# clock02.net
KiCad netlist of a schematic drawn in EAGLE
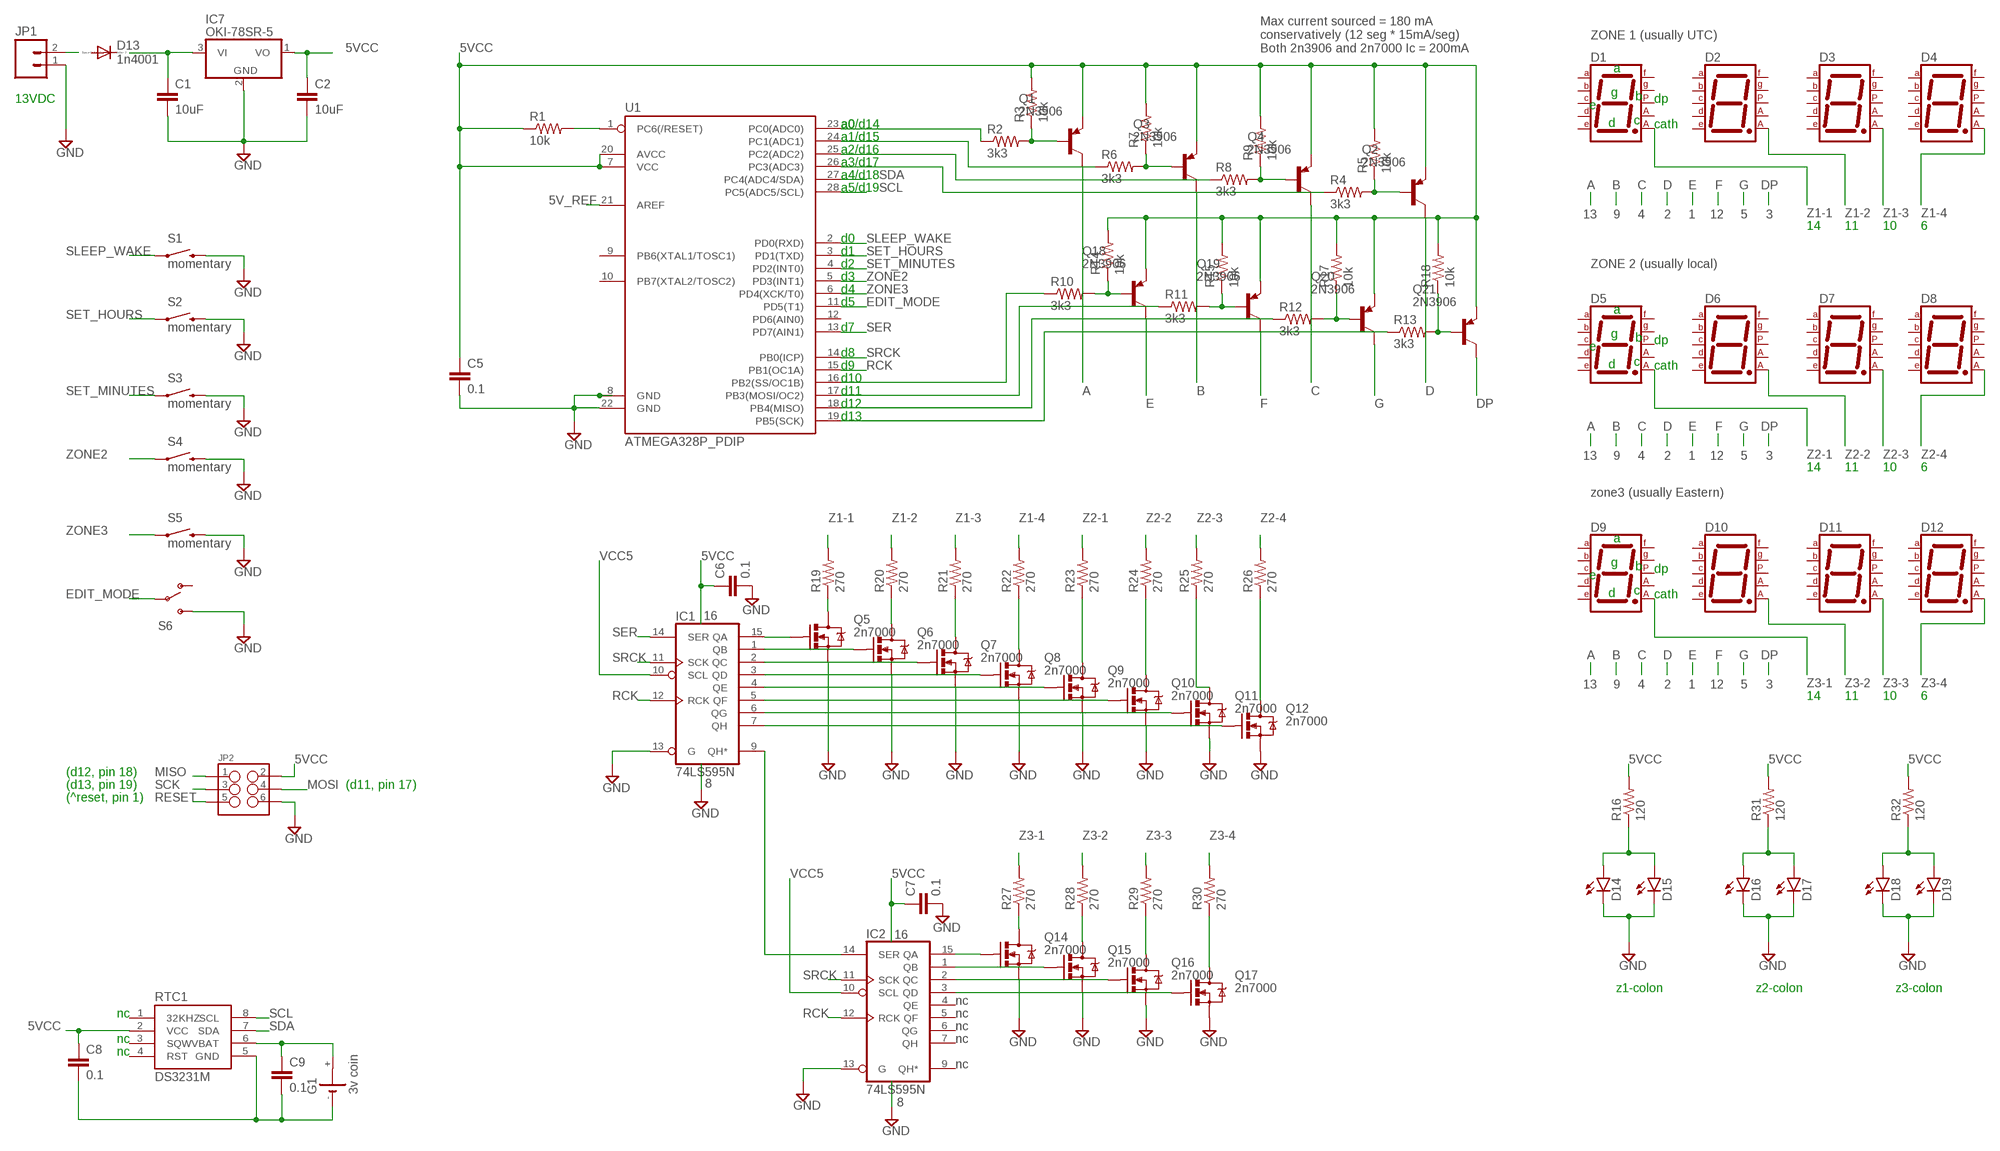
[diagram p0: schematic, sheet 1]

(export (version "E")
  (design (tool "Eeschema 10.0.6"))
  (components
    (comp (ref "C1")
      (value "10uF")
      (footprint "eagle-import:0603-CAP")
      (libsource (lib "eagle-import") (part "10NF/10000PF-50V-10%(0603)"))
    )
    (comp (ref "C2")
      (value "10uF")
      (footprint "eagle-import:0603-CAP")
      (libsource (lib "eagle-import") (part "10NF/10000PF-50V-10%(0603)"))
    )
    (comp (ref "C5")
      (value "0.1")
      (footprint "eagle-import:0603-CAP")
      (libsource (lib "eagle-import") (part "10NF/10000PF-50V-10%(0603)"))
    )
    (comp (ref "C6")
      (value "0.1")
      (footprint "eagle-import:0603-CAP")
      (libsource (lib "eagle-import") (part "10NF/10000PF-50V-10%(0603)"))
    )
    (comp (ref "C7")
      (value "0.1")
      (footprint "eagle-import:0603-CAP")
      (libsource (lib "eagle-import") (part "10NF/10000PF-50V-10%(0603)"))
    )
    (comp (ref "C8")
      (value "0.1")
      (footprint "eagle-import:0603-CAP")
      (libsource (lib "eagle-import") (part "10NF/10000PF-50V-10%(0603)"))
    )
    (comp (ref "C9")
      (value "0.1")
      (footprint "eagle-import:0603-CAP")
      (libsource (lib "eagle-import") (part "10NF/10000PF-50V-10%(0603)"))
    )
    (comp (ref "D1")
      (value "7SEG-CA")
      (footprint "eagle-import:7SEG-13")
      (libsource (lib "eagle-import") (part "7SEG-CA"))
    )
    (comp (ref "D2")
      (value "7SEG-CA")
      (footprint "eagle-import:7SEG-13")
      (libsource (lib "eagle-import") (part "7SEG-CA"))
    )
    (comp (ref "D3")
      (value "7SEG-CA")
      (footprint "eagle-import:7SEG-13")
      (libsource (lib "eagle-import") (part "7SEG-CA"))
    )
    (comp (ref "D4")
      (value "7SEG-CA")
      (footprint "eagle-import:7SEG-13")
      (libsource (lib "eagle-import") (part "7SEG-CA"))
    )
    (comp (ref "D5")
      (value "7SEG-CA")
      (footprint "eagle-import:7SEG-13")
      (libsource (lib "eagle-import") (part "7SEG-CA"))
    )
    (comp (ref "D6")
      (value "7SEG-CA")
      (footprint "eagle-import:7SEG-13")
      (libsource (lib "eagle-import") (part "7SEG-CA"))
    )
    (comp (ref "D7")
      (value "7SEG-CA")
      (footprint "eagle-import:7SEG-13")
      (libsource (lib "eagle-import") (part "7SEG-CA"))
    )
    (comp (ref "D8")
      (value "7SEG-CA")
      (footprint "eagle-import:7SEG-13")
      (libsource (lib "eagle-import") (part "7SEG-CA"))
    )
    (comp (ref "D9")
      (value "7SEG-CA")
      (footprint "eagle-import:7SEG-13")
      (libsource (lib "eagle-import") (part "7SEG-CA"))
    )
    (comp (ref "D10")
      (value "7SEG-CA")
      (footprint "eagle-import:7SEG-13")
      (libsource (lib "eagle-import") (part "7SEG-CA"))
    )
    (comp (ref "D11")
      (value "7SEG-CA")
      (footprint "eagle-import:7SEG-13")
      (libsource (lib "eagle-import") (part "7SEG-CA"))
    )
    (comp (ref "D12")
      (value "7SEG-CA")
      (footprint "eagle-import:7SEG-13")
      (libsource (lib "eagle-import") (part "7SEG-CA"))
    )
    (comp (ref "D13")
      (value "1n4001")
      (footprint "eagle-import:DO41-10")
      (libsource (lib "eagle-import") (part "1N4004"))
    )
    (comp (ref "D14")
      (value "LED3MM")
      (footprint "eagle-import:LED3MM")
      (libsource (lib "eagle-import") (part "LED3MM"))
    )
    (comp (ref "D15")
      (value "LED3MM")
      (footprint "eagle-import:LED3MM")
      (libsource (lib "eagle-import") (part "LED3MM"))
    )
    (comp (ref "D16")
      (value "LED3MM")
      (footprint "eagle-import:LED3MM")
      (libsource (lib "eagle-import") (part "LED3MM"))
    )
    (comp (ref "D17")
      (value "LED3MM")
      (footprint "eagle-import:LED3MM")
      (libsource (lib "eagle-import") (part "LED3MM"))
    )
    (comp (ref "D18")
      (value "LED3MM")
      (footprint "eagle-import:LED3MM")
      (libsource (lib "eagle-import") (part "LED3MM"))
    )
    (comp (ref "D19")
      (value "LED3MM")
      (footprint "eagle-import:LED3MM")
      (libsource (lib "eagle-import") (part "LED3MM"))
    )
    (comp (ref "G1")
      (value "3v coin")
      (footprint "eagle-import:CR2032H")
      (libsource (lib "eagle-import") (part "CR2032H"))
    )
    (comp (ref "IC1")
      (value "74LS595N")
      (footprint "eagle-import:DIL16")
      (libsource (lib "eagle-import") (part "74595NLS"))
    )
    (comp (ref "IC2")
      (value "74LS595N")
      (footprint "eagle-import:DIL16")
      (libsource (lib "eagle-import") (part "74595NLS"))
    )
    (comp (ref "IC7")
      (value "OKI-78SR-5")
      (footprint "eagle-import:TO92")
      (libsource (lib "eagle-import") (part "78ZL05"))
    )
    (comp (ref "JP1")
      (value "M02-JST-2-PTH-NO_SILK")
      (footprint "eagle-import:JST-2-PTH-NS")
      (libsource (lib "eagle-import") (part "M02-JST-2-PTH-NO_SILK"))
    )
    (comp (ref "JP2")
      (value "M03X2")
      (footprint "eagle-import:2X3_SMD")
      (libsource (lib "eagle-import") (part "M03X2"))
    )
    (comp (ref "Q1")
      (value "2N3906")
      (footprint "eagle-import:TO92")
      (libsource (lib "eagle-import") (part "2N3906"))
    )
    (comp (ref "Q2")
      (value "2N3906")
      (footprint "eagle-import:TO92")
      (libsource (lib "eagle-import") (part "2N3906"))
    )
    (comp (ref "Q3")
      (value "2N3906")
      (footprint "eagle-import:TO92")
      (libsource (lib "eagle-import") (part "2N3906"))
    )
    (comp (ref "Q4")
      (value "2N3906")
      (footprint "eagle-import:TO92")
      (libsource (lib "eagle-import") (part "2N3906"))
    )
    (comp (ref "Q5")
      (value "2n7000")
      (footprint "eagle-import:TO-92")
      (libsource (lib "eagle-import") (part "MOSFET-NCHANNEL2N7000"))
    )
    (comp (ref "Q6")
      (value "2n7000")
      (footprint "eagle-import:TO-92")
      (libsource (lib "eagle-import") (part "MOSFET-NCHANNEL2N7000"))
    )
    (comp (ref "Q7")
      (value "2n7000")
      (footprint "eagle-import:TO-92")
      (libsource (lib "eagle-import") (part "MOSFET-NCHANNEL2N7000"))
    )
    (comp (ref "Q8")
      (value "2n7000")
      (footprint "eagle-import:TO-92")
      (libsource (lib "eagle-import") (part "MOSFET-NCHANNEL2N7000"))
    )
    (comp (ref "Q9")
      (value "2n7000")
      (footprint "eagle-import:TO-92")
      (libsource (lib "eagle-import") (part "MOSFET-NCHANNEL2N7000"))
    )
    (comp (ref "Q10")
      (value "2n7000")
      (footprint "eagle-import:TO-92")
      (libsource (lib "eagle-import") (part "MOSFET-NCHANNEL2N7000"))
    )
    (comp (ref "Q11")
      (value "2n7000")
      (footprint "eagle-import:TO-92")
      (libsource (lib "eagle-import") (part "MOSFET-NCHANNEL2N7000"))
    )
    (comp (ref "Q12")
      (value "2n7000")
      (footprint "eagle-import:TO-92")
      (libsource (lib "eagle-import") (part "MOSFET-NCHANNEL2N7000"))
    )
    (comp (ref "Q14")
      (value "2n7000")
      (footprint "eagle-import:TO-92")
      (libsource (lib "eagle-import") (part "MOSFET-NCHANNEL2N7000"))
    )
    (comp (ref "Q15")
      (value "2n7000")
      (footprint "eagle-import:TO-92")
      (libsource (lib "eagle-import") (part "MOSFET-NCHANNEL2N7000"))
    )
    (comp (ref "Q16")
      (value "2n7000")
      (footprint "eagle-import:TO-92")
      (libsource (lib "eagle-import") (part "MOSFET-NCHANNEL2N7000"))
    )
    (comp (ref "Q17")
      (value "2n7000")
      (footprint "eagle-import:TO-92")
      (libsource (lib "eagle-import") (part "MOSFET-NCHANNEL2N7000"))
    )
    (comp (ref "Q18")
      (value "2N3906")
      (footprint "eagle-import:TO92")
      (libsource (lib "eagle-import") (part "2N3906"))
    )
    (comp (ref "Q19")
      (value "2N3906")
      (footprint "eagle-import:TO92")
      (libsource (lib "eagle-import") (part "2N3906"))
    )
    (comp (ref "Q20")
      (value "2N3906")
      (footprint "eagle-import:TO92")
      (libsource (lib "eagle-import") (part "2N3906"))
    )
    (comp (ref "Q21")
      (value "2N3906")
      (footprint "eagle-import:TO92")
      (libsource (lib "eagle-import") (part "2N3906"))
    )
    (comp (ref "R1")
      (value "10k")
      (footprint "eagle-import:AXIAL-0.3")
      (libsource (lib "eagle-import") (part "10KOHM-1/4W-1%(PTH)HORIZ"))
    )
    (comp (ref "R2")
      (value "3k3")
      (footprint "eagle-import:AXIAL-0.3")
      (libsource (lib "eagle-import") (part "10KOHM-1/4W-1%(PTH)HORIZ"))
    )
    (comp (ref "R3")
      (value "10k")
      (footprint "eagle-import:AXIAL-0.3")
      (libsource (lib "eagle-import") (part "10KOHM-1/4W-1%(PTH)HORIZ"))
    )
    (comp (ref "R4")
      (value "3k3")
      (footprint "eagle-import:AXIAL-0.3")
      (libsource (lib "eagle-import") (part "10KOHM-1/4W-1%(PTH)HORIZ"))
    )
    (comp (ref "R5")
      (value "10k")
      (footprint "eagle-import:AXIAL-0.3")
      (libsource (lib "eagle-import") (part "10KOHM-1/4W-1%(PTH)HORIZ"))
    )
    (comp (ref "R6")
      (value "3k3")
      (footprint "eagle-import:AXIAL-0.3")
      (libsource (lib "eagle-import") (part "10KOHM-1/4W-1%(PTH)HORIZ"))
    )
    (comp (ref "R7")
      (value "10k")
      (footprint "eagle-import:AXIAL-0.3")
      (libsource (lib "eagle-import") (part "10KOHM-1/4W-1%(PTH)HORIZ"))
    )
    (comp (ref "R8")
      (value "3k3")
      (footprint "eagle-import:AXIAL-0.3")
      (libsource (lib "eagle-import") (part "10KOHM-1/4W-1%(PTH)HORIZ"))
    )
    (comp (ref "R9")
      (value "10k")
      (footprint "eagle-import:AXIAL-0.3")
      (libsource (lib "eagle-import") (part "10KOHM-1/4W-1%(PTH)HORIZ"))
    )
    (comp (ref "R10")
      (value "3k3")
      (footprint "eagle-import:AXIAL-0.3")
      (libsource (lib "eagle-import") (part "10KOHM-1/4W-1%(PTH)HORIZ"))
    )
    (comp (ref "R11")
      (value "3k3")
      (footprint "eagle-import:AXIAL-0.3")
      (libsource (lib "eagle-import") (part "10KOHM-1/4W-1%(PTH)HORIZ"))
    )
    (comp (ref "R12")
      (value "3k3")
      (footprint "eagle-import:AXIAL-0.3")
      (libsource (lib "eagle-import") (part "10KOHM-1/4W-1%(PTH)HORIZ"))
    )
    (comp (ref "R13")
      (value "3k3")
      (footprint "eagle-import:AXIAL-0.3")
      (libsource (lib "eagle-import") (part "10KOHM-1/4W-1%(PTH)HORIZ"))
    )
    (comp (ref "R14")
      (value "10k")
      (footprint "eagle-import:AXIAL-0.3")
      (libsource (lib "eagle-import") (part "10KOHM-1/4W-1%(PTH)HORIZ"))
    )
    (comp (ref "R15")
      (value "10k")
      (footprint "eagle-import:AXIAL-0.3")
      (libsource (lib "eagle-import") (part "10KOHM-1/4W-1%(PTH)HORIZ"))
    )
    (comp (ref "R16")
      (value "120")
      (footprint "eagle-import:AXIAL-0.3")
      (libsource (lib "eagle-import") (part "10KOHM-1/4W-1%(PTH)HORIZ"))
    )
    (comp (ref "R17")
      (value "10k")
      (footprint "eagle-import:AXIAL-0.3")
      (libsource (lib "eagle-import") (part "10KOHM-1/4W-1%(PTH)HORIZ"))
    )
    (comp (ref "R18")
      (value "10k")
      (footprint "eagle-import:AXIAL-0.3")
      (libsource (lib "eagle-import") (part "10KOHM-1/4W-1%(PTH)HORIZ"))
    )
    (comp (ref "R19")
      (value "270")
      (footprint "eagle-import:AXIAL-0.3")
      (libsource (lib "eagle-import") (part "10KOHM-1/4W-1%(PTH)HORIZ"))
    )
    (comp (ref "R20")
      (value "270")
      (footprint "eagle-import:AXIAL-0.3")
      (libsource (lib "eagle-import") (part "10KOHM-1/4W-1%(PTH)HORIZ"))
    )
    (comp (ref "R21")
      (value "270")
      (footprint "eagle-import:AXIAL-0.3")
      (libsource (lib "eagle-import") (part "10KOHM-1/4W-1%(PTH)HORIZ"))
    )
    (comp (ref "R22")
      (value "270")
      (footprint "eagle-import:AXIAL-0.3")
      (libsource (lib "eagle-import") (part "10KOHM-1/4W-1%(PTH)HORIZ"))
    )
    (comp (ref "R23")
      (value "270")
      (footprint "eagle-import:AXIAL-0.3")
      (libsource (lib "eagle-import") (part "10KOHM-1/4W-1%(PTH)HORIZ"))
    )
    (comp (ref "R24")
      (value "270")
      (footprint "eagle-import:AXIAL-0.3")
      (libsource (lib "eagle-import") (part "10KOHM-1/4W-1%(PTH)HORIZ"))
    )
    (comp (ref "R25")
      (value "270")
      (footprint "eagle-import:AXIAL-0.3")
      (libsource (lib "eagle-import") (part "10KOHM-1/4W-1%(PTH)HORIZ"))
    )
    (comp (ref "R26")
      (value "270")
      (footprint "eagle-import:AXIAL-0.3")
      (libsource (lib "eagle-import") (part "10KOHM-1/4W-1%(PTH)HORIZ"))
    )
    (comp (ref "R27")
      (value "270")
      (footprint "eagle-import:AXIAL-0.3")
      (libsource (lib "eagle-import") (part "10KOHM-1/4W-1%(PTH)HORIZ"))
    )
    (comp (ref "R28")
      (value "270")
      (footprint "eagle-import:AXIAL-0.3")
      (libsource (lib "eagle-import") (part "10KOHM-1/4W-1%(PTH)HORIZ"))
    )
    (comp (ref "R29")
      (value "270")
      (footprint "eagle-import:AXIAL-0.3")
      (libsource (lib "eagle-import") (part "10KOHM-1/4W-1%(PTH)HORIZ"))
    )
    (comp (ref "R30")
      (value "270")
      (footprint "eagle-import:AXIAL-0.3")
      (libsource (lib "eagle-import") (part "10KOHM-1/4W-1%(PTH)HORIZ"))
    )
    (comp (ref "R31")
      (value "120")
      (footprint "eagle-import:AXIAL-0.3")
      (libsource (lib "eagle-import") (part "10KOHM-1/4W-1%(PTH)HORIZ"))
    )
    (comp (ref "R32")
      (value "120")
      (footprint "eagle-import:AXIAL-0.3")
      (libsource (lib "eagle-import") (part "10KOHM-1/4W-1%(PTH)HORIZ"))
    )
    (comp (ref "RTC1")
      (value "DS3231M")
      (footprint "eagle-import:SOIC8")
      (libsource (lib "eagle-import") (part "DS3231M"))
    )
    (comp (ref "S1")
      (value "momentary")
      (footprint "eagle-import:REED_SWITCH_PTH")
      (libsource (lib "eagle-import") (part "SWITCH-MOMENTARY-2PTH_REED"))
    )
    (comp (ref "S2")
      (value "momentary")
      (footprint "eagle-import:REED_SWITCH_PTH")
      (libsource (lib "eagle-import") (part "SWITCH-MOMENTARY-2PTH_REED"))
    )
    (comp (ref "S3")
      (value "momentary")
      (footprint "eagle-import:REED_SWITCH_PTH")
      (libsource (lib "eagle-import") (part "SWITCH-MOMENTARY-2PTH_REED"))
    )
    (comp (ref "S4")
      (value "momentary")
      (footprint "eagle-import:REED_SWITCH_PTH")
      (libsource (lib "eagle-import") (part "SWITCH-MOMENTARY-2PTH_REED"))
    )
    (comp (ref "S5")
      (value "momentary")
      (footprint "eagle-import:REED_SWITCH_PTH")
      (libsource (lib "eagle-import") (part "SWITCH-MOMENTARY-2PTH_REED"))
    )
    (comp (ref "S6")
      (value "SWITCH-SPDTPTH")
      (footprint "eagle-import:SWITCH-SPDT")
      (libsource (lib "eagle-import") (part "SWITCH-SPDTPTH"))
    )
    (comp (ref "U1")
      (value "ATMEGA328P_PDIP")
      (footprint "eagle-import:DIL28-3")
      (libsource (lib "eagle-import") (part "ATMEGA328P_PDIP"))
    )
  )
  (nets
    (net (code "1") (name "/5VCC") (class "Default")
      (node (ref "C2") (pin "1") (pinfunction "1_1") (pintype "passive"))
      (node (ref "C5") (pin "1") (pinfunction "1_1") (pintype "passive"))
      (node (ref "C6") (pin "1") (pinfunction "1_1") (pintype "passive"))
      (node (ref "C7") (pin "1") (pinfunction "1_1") (pintype "passive"))
      (node (ref "C8") (pin "1") (pinfunction "1_1") (pintype "passive"))
      (node (ref "IC7") (pin "1") (pinfunction "VO_1") (pintype "passive"))
      (node (ref "JP2") (pin "2") (pinfunction "2_2") (pintype "bidirectional"))
      (node (ref "Q1") (pin "3") (pinfunction "E_3") (pintype "passive"))
      (node (ref "Q18") (pin "3") (pinfunction "E_3") (pintype "passive"))
      (node (ref "Q19") (pin "3") (pinfunction "E_3") (pintype "passive"))
      (node (ref "Q2") (pin "3") (pinfunction "E_3") (pintype "passive"))
      (node (ref "Q20") (pin "3") (pinfunction "E_3") (pintype "passive"))
      (node (ref "Q21") (pin "3") (pinfunction "E_3") (pintype "passive"))
      (node (ref "Q3") (pin "3") (pinfunction "E_3") (pintype "passive"))
      (node (ref "Q4") (pin "3") (pinfunction "E_3") (pintype "passive"))
      (node (ref "R1") (pin "P$1") (pinfunction "1_P$1") (pintype "passive"))
      (node (ref "R14") (pin "P$2") (pinfunction "2_P$2") (pintype "passive"))
      (node (ref "R15") (pin "P$2") (pinfunction "2_P$2") (pintype "passive"))
      (node (ref "R16") (pin "P$2") (pinfunction "2_P$2") (pintype "passive"))
      (node (ref "R17") (pin "P$2") (pinfunction "2_P$2") (pintype "passive"))
      (node (ref "R18") (pin "P$2") (pinfunction "2_P$2") (pintype "passive"))
      (node (ref "R3") (pin "P$2") (pinfunction "2_P$2") (pintype "passive"))
      (node (ref "R31") (pin "P$2") (pinfunction "2_P$2") (pintype "passive"))
      (node (ref "R32") (pin "P$2") (pinfunction "2_P$2") (pintype "passive"))
      (node (ref "R5") (pin "P$2") (pinfunction "2_P$2") (pintype "passive"))
      (node (ref "R7") (pin "P$2") (pinfunction "2_P$2") (pintype "passive"))
      (node (ref "R9") (pin "P$2") (pinfunction "2_P$2") (pintype "passive"))
      (node (ref "RTC1") (pin "2") (pinfunction "VCC_2") (pintype "power_in"))
      (node (ref "U1") (pin "20") (pinfunction "AVCC_20") (pintype "bidirectional"))
      (node (ref "U1") (pin "7") (pinfunction "VCC_7") (pintype "bidirectional"))
    )
    (net (code "2") (name "/5V_REF") (class "Default")
      (node (ref "U1") (pin "21") (pinfunction "AREF_21") (pintype "bidirectional"))
    )
    (net (code "3") (name "/A") (class "Default")
      (node (ref "Q1") (pin "1") (pinfunction "C_1") (pintype "passive"))
    )
    (net (code "4") (name "/B") (class "Default")
      (node (ref "Q3") (pin "1") (pinfunction "C_1") (pintype "passive"))
    )
    (net (code "5") (name "/C") (class "Default")
      (node (ref "Q4") (pin "1") (pinfunction "C_1") (pintype "passive"))
    )
    (net (code "6") (name "/D") (class "Default")
      (node (ref "Q2") (pin "1") (pinfunction "C_1") (pintype "passive"))
    )
    (net (code "7") (name "/DP") (class "Default")
      (node (ref "Q21") (pin "1") (pinfunction "C_1") (pintype "passive"))
    )
    (net (code "8") (name "/E") (class "Default")
      (node (ref "Q18") (pin "1") (pinfunction "C_1") (pintype "passive"))
    )
    (net (code "9") (name "/EDIT_MODE") (class "Default")
      (node (ref "S6") (pin "2") (pinfunction "P_2") (pintype "passive"))
      (node (ref "U1") (pin "11") (pinfunction "PD5(T1)_11") (pintype "bidirectional"))
    )
    (net (code "10") (name "/F") (class "Default")
      (node (ref "Q19") (pin "1") (pinfunction "C_1") (pintype "passive"))
    )
    (net (code "11") (name "/G") (class "Default")
      (node (ref "Q20") (pin "1") (pinfunction "C_1") (pintype "passive"))
    )
    (net (code "12") (name "/MISO") (class "Default")
      (node (ref "JP2") (pin "1") (pinfunction "1_1") (pintype "bidirectional"))
    )
    (net (code "13") (name "/MOSI") (class "Default")
      (node (ref "JP2") (pin "4") (pinfunction "4_4") (pintype "bidirectional"))
    )
    (net (code "14") (name "/RCK") (class "Default")
      (node (ref "IC1") (pin "12") (pinfunction "RCK_12") (pintype "input"))
      (node (ref "IC2") (pin "12") (pinfunction "RCK_12") (pintype "input"))
      (node (ref "U1") (pin "15") (pinfunction "PB1(OC1A)_15") (pintype "bidirectional"))
    )
    (net (code "15") (name "/RESET") (class "Default")
      (node (ref "JP2") (pin "5") (pinfunction "5_5") (pintype "bidirectional"))
    )
    (net (code "16") (name "/SCK") (class "Default")
      (node (ref "JP2") (pin "3") (pinfunction "3_3") (pintype "bidirectional"))
    )
    (net (code "17") (name "/SCL") (class "Default")
      (node (ref "RTC1") (pin "8") (pinfunction "SCL_8") (pintype "bidirectional"))
      (node (ref "U1") (pin "28") (pinfunction "PC5(ADC5/SCL)_28") (pintype "bidirectional"))
    )
    (net (code "18") (name "/SDA") (class "Default")
      (node (ref "RTC1") (pin "7") (pinfunction "SDA_7") (pintype "bidirectional"))
      (node (ref "U1") (pin "27") (pinfunction "PC4(ADC4/SDA)_27") (pintype "bidirectional"))
    )
    (net (code "19") (name "/SER") (class "Default")
      (node (ref "IC1") (pin "14") (pinfunction "SER_14") (pintype "input"))
      (node (ref "U1") (pin "13") (pinfunction "PD7(AIN1)_13") (pintype "bidirectional"))
    )
    (net (code "20") (name "/SET_HOURS") (class "Default")
      (node (ref "S2") (pin "P$1") (pinfunction "1_P$1") (pintype "passive"))
      (node (ref "U1") (pin "3") (pinfunction "PD1(TXD)_3") (pintype "bidirectional"))
    )
    (net (code "21") (name "/SET_MINUTES") (class "Default")
      (node (ref "S3") (pin "P$1") (pinfunction "1_P$1") (pintype "passive"))
      (node (ref "U1") (pin "4") (pinfunction "PD2(INT0)_4") (pintype "bidirectional"))
    )
    (net (code "22") (name "/SLEEP_WAKE") (class "Default")
      (node (ref "S1") (pin "P$1") (pinfunction "1_P$1") (pintype "passive"))
      (node (ref "U1") (pin "2") (pinfunction "PD0(RXD)_2") (pintype "bidirectional"))
    )
    (net (code "23") (name "/SRCK") (class "Default")
      (node (ref "IC1") (pin "11") (pinfunction "SCK_11") (pintype "input"))
      (node (ref "IC2") (pin "11") (pinfunction "SCK_11") (pintype "input"))
      (node (ref "U1") (pin "14") (pinfunction "PB0(ICP)_14") (pintype "bidirectional"))
    )
    (net (code "24") (name "/VCC5") (class "Default")
      (node (ref "IC1") (pin "10") (pinfunction "SCL_10") (pintype "input"))
      (node (ref "IC2") (pin "10") (pinfunction "SCL_10") (pintype "input"))
    )
    (net (code "25") (name "/Z1-1") (class "Default")
      (node (ref "D1") (pin "8") (pinfunction "CA2_8") (pintype "passive"))
      (node (ref "R19") (pin "P$2") (pinfunction "2_P$2") (pintype "passive"))
    )
    (net (code "26") (name "/Z1-2") (class "Default")
      (node (ref "D2") (pin "8") (pinfunction "CA2_8") (pintype "passive"))
      (node (ref "R20") (pin "P$2") (pinfunction "2_P$2") (pintype "passive"))
    )
    (net (code "27") (name "/Z1-3") (class "Default")
      (node (ref "D3") (pin "8") (pinfunction "CA2_8") (pintype "passive"))
      (node (ref "R21") (pin "P$2") (pinfunction "2_P$2") (pintype "passive"))
    )
    (net (code "28") (name "/Z1-4") (class "Default")
      (node (ref "D4") (pin "8") (pinfunction "CA2_8") (pintype "passive"))
      (node (ref "R22") (pin "P$2") (pinfunction "2_P$2") (pintype "passive"))
    )
    (net (code "29") (name "/Z2-1") (class "Default")
      (node (ref "D5") (pin "8") (pinfunction "CA2_8") (pintype "passive"))
      (node (ref "R23") (pin "P$2") (pinfunction "2_P$2") (pintype "passive"))
    )
    (net (code "30") (name "/Z2-2") (class "Default")
      (node (ref "D6") (pin "8") (pinfunction "CA2_8") (pintype "passive"))
      (node (ref "R24") (pin "P$2") (pinfunction "2_P$2") (pintype "passive"))
    )
    (net (code "31") (name "/Z2-3") (class "Default")
      (node (ref "D7") (pin "8") (pinfunction "CA2_8") (pintype "passive"))
      (node (ref "R25") (pin "P$2") (pinfunction "2_P$2") (pintype "passive"))
    )
    (net (code "32") (name "/Z2-4") (class "Default")
      (node (ref "D8") (pin "8") (pinfunction "CA2_8") (pintype "passive"))
      (node (ref "R26") (pin "P$2") (pinfunction "2_P$2") (pintype "passive"))
    )
    (net (code "33") (name "/Z3-1") (class "Default")
      (node (ref "D9") (pin "8") (pinfunction "CA2_8") (pintype "passive"))
      (node (ref "R27") (pin "P$2") (pinfunction "2_P$2") (pintype "passive"))
    )
    (net (code "34") (name "/Z3-2") (class "Default")
      (node (ref "D10") (pin "8") (pinfunction "CA2_8") (pintype "passive"))
      (node (ref "R28") (pin "P$2") (pinfunction "2_P$2") (pintype "passive"))
    )
    (net (code "35") (name "/Z3-3") (class "Default")
      (node (ref "D11") (pin "8") (pinfunction "CA2_8") (pintype "passive"))
      (node (ref "R29") (pin "P$2") (pinfunction "2_P$2") (pintype "passive"))
    )
    (net (code "36") (name "/Z3-4") (class "Default")
      (node (ref "D12") (pin "8") (pinfunction "CA2_8") (pintype "passive"))
      (node (ref "R30") (pin "P$2") (pinfunction "2_P$2") (pintype "passive"))
    )
    (net (code "37") (name "/ZONE2") (class "Default")
      (node (ref "S4") (pin "P$1") (pinfunction "1_P$1") (pintype "passive"))
      (node (ref "U1") (pin "5") (pinfunction "PD3(INT1)_5") (pintype "bidirectional"))
    )
    (net (code "38") (name "/ZONE3") (class "Default")
      (node (ref "S5") (pin "P$1") (pinfunction "1_P$1") (pintype "passive"))
      (node (ref "U1") (pin "6") (pinfunction "PD4(XCK/T0)_6") (pintype "bidirectional"))
    )
    (net (code "39") (name "GND") (class "Default")
      (node (ref "C1") (pin "2") (pinfunction "2_2") (pintype "passive"))
      (node (ref "C2") (pin "2") (pinfunction "2_2") (pintype "passive"))
      (node (ref "C5") (pin "2") (pinfunction "2_2") (pintype "passive"))
      (node (ref "C6") (pin "2") (pinfunction "2_2") (pintype "passive"))
      (node (ref "C7") (pin "2") (pinfunction "2_2") (pintype "passive"))
      (node (ref "D14") (pin "K") (pinfunction "C_K") (pintype "passive"))
      (node (ref "D15") (pin "K") (pinfunction "C_K") (pintype "passive"))
      (node (ref "D16") (pin "K") (pinfunction "C_K") (pintype "passive"))
      (node (ref "D17") (pin "K") (pinfunction "C_K") (pintype "passive"))
      (node (ref "D18") (pin "K") (pinfunction "C_K") (pintype "passive"))
      (node (ref "D19") (pin "K") (pinfunction "C_K") (pintype "passive"))
      (node (ref "IC1") (pin "13") (pinfunction "G_13") (pintype "input"))
      (node (ref "IC2") (pin "13") (pinfunction "G_13") (pintype "input"))
      (node (ref "IC7") (pin "2") (pinfunction "GND_2") (pintype "passive"))
      (node (ref "JP1") (pin "1") (pinfunction "1_1") (pintype "passive"))
      (node (ref "JP2") (pin "6") (pinfunction "6_6") (pintype "bidirectional"))
      (node (ref "Q10") (pin "1") (pinfunction "S_1") (pintype "passive"))
      (node (ref "Q11") (pin "1") (pinfunction "S_1") (pintype "passive"))
      (node (ref "Q12") (pin "1") (pinfunction "S_1") (pintype "passive"))
      (node (ref "Q14") (pin "1") (pinfunction "S_1") (pintype "passive"))
      (node (ref "Q15") (pin "1") (pinfunction "S_1") (pintype "passive"))
      (node (ref "Q16") (pin "1") (pinfunction "S_1") (pintype "passive"))
      (node (ref "Q17") (pin "1") (pinfunction "S_1") (pintype "passive"))
      (node (ref "Q5") (pin "1") (pinfunction "S_1") (pintype "passive"))
      (node (ref "Q6") (pin "1") (pinfunction "S_1") (pintype "passive"))
      (node (ref "Q7") (pin "1") (pinfunction "S_1") (pintype "passive"))
      (node (ref "Q8") (pin "1") (pinfunction "S_1") (pintype "passive"))
      (node (ref "Q9") (pin "1") (pinfunction "S_1") (pintype "passive"))
      (node (ref "S1") (pin "P$2") (pinfunction "2_P$2") (pintype "passive"))
      (node (ref "S2") (pin "P$2") (pinfunction "2_P$2") (pintype "passive"))
      (node (ref "S3") (pin "P$2") (pinfunction "2_P$2") (pintype "passive"))
      (node (ref "S4") (pin "P$2") (pinfunction "2_P$2") (pintype "passive"))
      (node (ref "S5") (pin "P$2") (pinfunction "2_P$2") (pintype "passive"))
      (node (ref "S6") (pin "3") (pinfunction "S_3") (pintype "passive"))
      (node (ref "U1") (pin "22") (pinfunction "GND_22") (pintype "bidirectional"))
      (node (ref "U1") (pin "8") (pinfunction "GND_8") (pintype "bidirectional"))
    )
    (net (code "40") (name "Net-(IC1A-QA)") (class "Default")
      (node (ref "IC1") (pin "15") (pinfunction "QA_15") (pintype "tri_state"))
      (node (ref "Q5") (pin "2") (pinfunction "G_2") (pintype "passive"))
    )
    (net (code "41") (name "Net-(IC1A-QB)") (class "Default")
      (node (ref "IC1") (pin "1") (pinfunction "QB_1") (pintype "tri_state"))
      (node (ref "Q6") (pin "2") (pinfunction "G_2") (pintype "passive"))
    )
    (net (code "42") (name "Net-(IC1A-QC)") (class "Default")
      (node (ref "IC1") (pin "2") (pinfunction "QC_2") (pintype "tri_state"))
      (node (ref "Q7") (pin "2") (pinfunction "G_2") (pintype "passive"))
    )
    (net (code "43") (name "Net-(IC1A-QD)") (class "Default")
      (node (ref "IC1") (pin "3") (pinfunction "QD_3") (pintype "tri_state"))
      (node (ref "Q8") (pin "2") (pinfunction "G_2") (pintype "passive"))
    )
    (net (code "44") (name "Net-(IC1A-QE)") (class "Default")
      (node (ref "IC1") (pin "4") (pinfunction "QE_4") (pintype "tri_state"))
      (node (ref "Q9") (pin "2") (pinfunction "G_2") (pintype "passive"))
    )
    (net (code "45") (name "Net-(IC1A-QF)") (class "Default")
      (node (ref "IC1") (pin "5") (pinfunction "QF_5") (pintype "tri_state"))
      (node (ref "Q10") (pin "2") (pinfunction "G_2") (pintype "passive"))
    )
    (net (code "46") (name "Net-(IC1A-QG)") (class "Default")
      (node (ref "IC1") (pin "6") (pinfunction "QG_6") (pintype "tri_state"))
      (node (ref "Q11") (pin "2") (pinfunction "G_2") (pintype "passive"))
    )
    (net (code "47") (name "Net-(IC1A-QH)") (class "Default")
      (node (ref "IC1") (pin "7") (pinfunction "QH_7") (pintype "tri_state"))
      (node (ref "Q12") (pin "2") (pinfunction "G_2") (pintype "passive"))
    )
    (net (code "48") (name "Net-(IC1A-QH*)") (class "Default")
      (node (ref "IC1") (pin "9") (pinfunction "QH*_9") (pintype "tri_state"))
      (node (ref "IC2") (pin "14") (pinfunction "SER_14") (pintype "input"))
    )
    (net (code "49") (name "Net-(IC2A-QA)") (class "Default")
      (node (ref "IC2") (pin "15") (pinfunction "QA_15") (pintype "tri_state"))
      (node (ref "Q14") (pin "2") (pinfunction "G_2") (pintype "passive"))
    )
    (net (code "50") (name "Net-(IC2A-QB)") (class "Default")
      (node (ref "IC2") (pin "1") (pinfunction "QB_1") (pintype "tri_state"))
      (node (ref "Q15") (pin "2") (pinfunction "G_2") (pintype "passive"))
    )
    (net (code "51") (name "Net-(IC2A-QC)") (class "Default")
      (node (ref "IC2") (pin "2") (pinfunction "QC_2") (pintype "tri_state"))
      (node (ref "Q16") (pin "2") (pinfunction "G_2") (pintype "passive"))
    )
    (net (code "52") (name "Net-(IC2A-QD)") (class "Default")
      (node (ref "IC2") (pin "3") (pinfunction "QD_3") (pintype "tri_state"))
      (node (ref "Q17") (pin "2") (pinfunction "G_2") (pintype "passive"))
    )
    (net (code "53") (name "Net-(IC7-VI)") (class "Default")
      (node (ref "C1") (pin "1") (pinfunction "1_1") (pintype "passive"))
      (node (ref "IC7") (pin "3") (pinfunction "VI_3") (pintype "input"))
    )
    (net (code "54") (name "Net-(Q1-B)") (class "Default")
      (node (ref "Q1") (pin "2") (pinfunction "B_2") (pintype "passive"))
      (node (ref "R2") (pin "P$2") (pinfunction "2_P$2") (pintype "passive"))
      (node (ref "R3") (pin "P$1") (pinfunction "1_P$1") (pintype "passive"))
    )
    (net (code "55") (name "Net-(Q2-B)") (class "Default")
      (node (ref "Q2") (pin "2") (pinfunction "B_2") (pintype "passive"))
      (node (ref "R4") (pin "P$2") (pinfunction "2_P$2") (pintype "passive"))
      (node (ref "R5") (pin "P$1") (pinfunction "1_P$1") (pintype "passive"))
    )
    (net (code "56") (name "Net-(Q3-B)") (class "Default")
      (node (ref "Q3") (pin "2") (pinfunction "B_2") (pintype "passive"))
      (node (ref "R6") (pin "P$2") (pinfunction "2_P$2") (pintype "passive"))
      (node (ref "R7") (pin "P$1") (pinfunction "1_P$1") (pintype "passive"))
    )
    (net (code "57") (name "Net-(Q4-B)") (class "Default")
      (node (ref "Q4") (pin "2") (pinfunction "B_2") (pintype "passive"))
      (node (ref "R8") (pin "P$2") (pinfunction "2_P$2") (pintype "passive"))
      (node (ref "R9") (pin "P$1") (pinfunction "1_P$1") (pintype "passive"))
    )
    (net (code "58") (name "Net-(Q5-D)") (class "Default")
      (node (ref "Q5") (pin "3") (pinfunction "D_3") (pintype "passive"))
      (node (ref "R19") (pin "P$1") (pinfunction "1_P$1") (pintype "passive"))
    )
    (net (code "59") (name "Net-(Q6-D)") (class "Default")
      (node (ref "Q6") (pin "3") (pinfunction "D_3") (pintype "passive"))
      (node (ref "R20") (pin "P$1") (pinfunction "1_P$1") (pintype "passive"))
    )
    (net (code "60") (name "Net-(Q7-D)") (class "Default")
      (node (ref "Q7") (pin "3") (pinfunction "D_3") (pintype "passive"))
      (node (ref "R21") (pin "P$1") (pinfunction "1_P$1") (pintype "passive"))
    )
    (net (code "61") (name "Net-(Q8-D)") (class "Default")
      (node (ref "Q8") (pin "3") (pinfunction "D_3") (pintype "passive"))
      (node (ref "R22") (pin "P$1") (pinfunction "1_P$1") (pintype "passive"))
    )
    (net (code "62") (name "Net-(Q9-D)") (class "Default")
      (node (ref "Q9") (pin "3") (pinfunction "D_3") (pintype "passive"))
      (node (ref "R23") (pin "P$1") (pinfunction "1_P$1") (pintype "passive"))
    )
    (net (code "63") (name "Net-(Q10-D)") (class "Default")
      (node (ref "Q10") (pin "3") (pinfunction "D_3") (pintype "passive"))
      (node (ref "R24") (pin "P$1") (pinfunction "1_P$1") (pintype "passive"))
    )
    (net (code "64") (name "Net-(Q11-D)") (class "Default")
      (node (ref "Q11") (pin "3") (pinfunction "D_3") (pintype "passive"))
      (node (ref "R25") (pin "P$1") (pinfunction "1_P$1") (pintype "passive"))
    )
    (net (code "65") (name "Net-(Q12-D)") (class "Default")
      (node (ref "Q12") (pin "3") (pinfunction "D_3") (pintype "passive"))
      (node (ref "R26") (pin "P$1") (pinfunction "1_P$1") (pintype "passive"))
    )
    (net (code "66") (name "Net-(Q14-D)") (class "Default")
      (node (ref "Q14") (pin "3") (pinfunction "D_3") (pintype "passive"))
      (node (ref "R27") (pin "P$1") (pinfunction "1_P$1") (pintype "passive"))
    )
    (net (code "67") (name "Net-(Q15-D)") (class "Default")
      (node (ref "Q15") (pin "3") (pinfunction "D_3") (pintype "passive"))
      (node (ref "R28") (pin "P$1") (pinfunction "1_P$1") (pintype "passive"))
    )
    (net (code "68") (name "Net-(Q16-D)") (class "Default")
      (node (ref "Q16") (pin "3") (pinfunction "D_3") (pintype "passive"))
      (node (ref "R29") (pin "P$1") (pinfunction "1_P$1") (pintype "passive"))
    )
    (net (code "69") (name "Net-(Q17-D)") (class "Default")
      (node (ref "Q17") (pin "3") (pinfunction "D_3") (pintype "passive"))
      (node (ref "R30") (pin "P$1") (pinfunction "1_P$1") (pintype "passive"))
    )
    (net (code "70") (name "Net-(Q18-B)") (class "Default")
      (node (ref "Q18") (pin "2") (pinfunction "B_2") (pintype "passive"))
      (node (ref "R10") (pin "P$2") (pinfunction "2_P$2") (pintype "passive"))
      (node (ref "R14") (pin "P$1") (pinfunction "1_P$1") (pintype "passive"))
    )
    (net (code "71") (name "Net-(Q19-B)") (class "Default")
      (node (ref "Q19") (pin "2") (pinfunction "B_2") (pintype "passive"))
      (node (ref "R11") (pin "P$2") (pinfunction "2_P$2") (pintype "passive"))
      (node (ref "R15") (pin "P$1") (pinfunction "1_P$1") (pintype "passive"))
    )
    (net (code "72") (name "Net-(Q20-B)") (class "Default")
      (node (ref "Q20") (pin "2") (pinfunction "B_2") (pintype "passive"))
      (node (ref "R12") (pin "P$2") (pinfunction "2_P$2") (pintype "passive"))
      (node (ref "R17") (pin "P$1") (pinfunction "1_P$1") (pintype "passive"))
    )
    (net (code "73") (name "Net-(Q21-B)") (class "Default")
      (node (ref "Q21") (pin "2") (pinfunction "B_2") (pintype "passive"))
      (node (ref "R13") (pin "P$2") (pinfunction "2_P$2") (pintype "passive"))
      (node (ref "R18") (pin "P$1") (pinfunction "1_P$1") (pintype "passive"))
    )
    (net (code "74") (name "Net-(R1-2)") (class "Default")
      (node (ref "R1") (pin "P$2") (pinfunction "2_P$2") (pintype "passive"))
      (node (ref "U1") (pin "1") (pinfunction "PC6(/RESET)_1") (pintype "bidirectional"))
    )
    (net (code "75") (name "Net-(R2-1)") (class "Default")
      (node (ref "R2") (pin "P$1") (pinfunction "1_P$1") (pintype "passive"))
      (node (ref "U1") (pin "23") (pinfunction "PC0(ADC0)_23") (pintype "bidirectional"))
    )
    (net (code "76") (name "Net-(R4-1)") (class "Default")
      (node (ref "R4") (pin "P$1") (pinfunction "1_P$1") (pintype "passive"))
      (node (ref "U1") (pin "26") (pinfunction "PC3(ADC3)_26") (pintype "bidirectional"))
    )
    (net (code "77") (name "Net-(R6-1)") (class "Default")
      (node (ref "R6") (pin "P$1") (pinfunction "1_P$1") (pintype "passive"))
      (node (ref "U1") (pin "24") (pinfunction "PC1(ADC1)_24") (pintype "bidirectional"))
    )
    (net (code "78") (name "Net-(R8-1)") (class "Default")
      (node (ref "R8") (pin "P$1") (pinfunction "1_P$1") (pintype "passive"))
      (node (ref "U1") (pin "25") (pinfunction "PC2(ADC2)_25") (pintype "bidirectional"))
    )
    (net (code "79") (name "Net-(R10-1)") (class "Default")
      (node (ref "R10") (pin "P$1") (pinfunction "1_P$1") (pintype "passive"))
      (node (ref "U1") (pin "16") (pinfunction "PB2(SS/OC1B)_16") (pintype "bidirectional"))
    )
    (net (code "80") (name "Net-(R11-1)") (class "Default")
      (node (ref "R11") (pin "P$1") (pinfunction "1_P$1") (pintype "passive"))
      (node (ref "U1") (pin "17") (pinfunction "PB3(MOSI/OC2)_17") (pintype "bidirectional"))
    )
    (net (code "81") (name "Net-(R12-1)") (class "Default")
      (node (ref "R12") (pin "P$1") (pinfunction "1_P$1") (pintype "passive"))
      (node (ref "U1") (pin "18") (pinfunction "PB4(MISO)_18") (pintype "bidirectional"))
    )
    (net (code "82") (name "Net-(R13-1)") (class "Default")
      (node (ref "R13") (pin "P$1") (pinfunction "1_P$1") (pintype "passive"))
      (node (ref "U1") (pin "19") (pinfunction "PB5(SCK)_19") (pintype "bidirectional"))
    )
    (net (code "83") (name "Net-(R16-1)") (class "Default")
      (node (ref "D14") (pin "A") (pinfunction "A_A") (pintype "passive"))
      (node (ref "D15") (pin "A") (pinfunction "A_A") (pintype "passive"))
      (node (ref "R16") (pin "P$1") (pinfunction "1_P$1") (pintype "passive"))
    )
    (net (code "84") (name "Net-(R31-1)") (class "Default")
      (node (ref "D16") (pin "A") (pinfunction "A_A") (pintype "passive"))
      (node (ref "D17") (pin "A") (pinfunction "A_A") (pintype "passive"))
      (node (ref "R31") (pin "P$1") (pinfunction "1_P$1") (pintype "passive"))
    )
    (net (code "85") (name "Net-(R32-1)") (class "Default")
      (node (ref "D18") (pin "A") (pinfunction "A_A") (pintype "passive"))
      (node (ref "D19") (pin "A") (pinfunction "A_A") (pintype "passive"))
      (node (ref "R32") (pin "P$1") (pinfunction "1_P$1") (pintype "passive"))
    )
    (net (code "86") (name "Net-(RTC1-GND)") (class "Default")
      (node (ref "C8") (pin "2") (pinfunction "2_2") (pintype "passive"))
      (node (ref "C9") (pin "2") (pinfunction "2_2") (pintype "passive"))
      (node (ref "G1") (pin "-") (pinfunction "-_-") (pintype "passive"))
      (node (ref "RTC1") (pin "5") (pinfunction "GND_5") (pintype "power_in"))
    )
    (net (code "87") (name "Net-(RTC1-VBAT)") (class "Default")
      (node (ref "C9") (pin "1") (pinfunction "1_1") (pintype "passive"))
      (node (ref "G1") (pin "+") (pinfunction "+_+") (pintype "passive"))
      (node (ref "RTC1") (pin "6") (pinfunction "VBAT_6") (pintype "power_in"))
    )
    (net (code "88") (name "unconnected-(D1-A-Pad7)") (class "Default")
      (node (ref "D1") (pin "7") (pinfunction "A_7") (pintype "passive"))
    )
    (net (code "89") (name "unconnected-(D1-B-Pad6)") (class "Default")
      (node (ref "D1") (pin "6") (pinfunction "B_6") (pintype "passive"))
    )
    (net (code "90") (name "unconnected-(D1-C-Pad4)") (class "Default")
      (node (ref "D1") (pin "4") (pinfunction "C_4") (pintype "passive"))
    )
    (net (code "91") (name "unconnected-(D1-CA1-Pad3)") (class "Default")
      (node (ref "D1") (pin "3") (pinfunction "CA1_3") (pintype "passive"))
    )
    (net (code "92") (name "unconnected-(D1-D-Pad2)") (class "Default")
      (node (ref "D1") (pin "2") (pinfunction "D_2") (pintype "passive"))
    )
    (net (code "93") (name "unconnected-(D1-DP-Pad5)") (class "Default")
      (node (ref "D1") (pin "5") (pinfunction "DP_5") (pintype "passive"))
    )
    (net (code "94") (name "unconnected-(D1-E-Pad1)") (class "Default")
      (node (ref "D1") (pin "1") (pinfunction "E_1") (pintype "passive"))
    )
    (net (code "95") (name "unconnected-(D1-F-Pad9)") (class "Default")
      (node (ref "D1") (pin "9") (pinfunction "F_9") (pintype "passive"))
    )
    (net (code "96") (name "unconnected-(D1-G-Pad10)") (class "Default")
      (node (ref "D1") (pin "10") (pinfunction "G_10") (pintype "passive"))
    )
    (net (code "97") (name "unconnected-(D2-A-Pad7)") (class "Default")
      (node (ref "D2") (pin "7") (pinfunction "A_7") (pintype "passive"))
    )
    (net (code "98") (name "unconnected-(D2-B-Pad6)") (class "Default")
      (node (ref "D2") (pin "6") (pinfunction "B_6") (pintype "passive"))
    )
    (net (code "99") (name "unconnected-(D2-C-Pad4)") (class "Default")
      (node (ref "D2") (pin "4") (pinfunction "C_4") (pintype "passive"))
    )
    (net (code "100") (name "unconnected-(D2-CA1-Pad3)") (class "Default")
      (node (ref "D2") (pin "3") (pinfunction "CA1_3") (pintype "passive"))
    )
    (net (code "101") (name "unconnected-(D2-D-Pad2)") (class "Default")
      (node (ref "D2") (pin "2") (pinfunction "D_2") (pintype "passive"))
    )
    (net (code "102") (name "unconnected-(D2-DP-Pad5)") (class "Default")
      (node (ref "D2") (pin "5") (pinfunction "DP_5") (pintype "passive"))
    )
    (net (code "103") (name "unconnected-(D2-E-Pad1)") (class "Default")
      (node (ref "D2") (pin "1") (pinfunction "E_1") (pintype "passive"))
    )
    (net (code "104") (name "unconnected-(D2-F-Pad9)") (class "Default")
      (node (ref "D2") (pin "9") (pinfunction "F_9") (pintype "passive"))
    )
    (net (code "105") (name "unconnected-(D2-G-Pad10)") (class "Default")
      (node (ref "D2") (pin "10") (pinfunction "G_10") (pintype "passive"))
    )
    (net (code "106") (name "unconnected-(D3-A-Pad7)") (class "Default")
      (node (ref "D3") (pin "7") (pinfunction "A_7") (pintype "passive"))
    )
    (net (code "107") (name "unconnected-(D3-B-Pad6)") (class "Default")
      (node (ref "D3") (pin "6") (pinfunction "B_6") (pintype "passive"))
    )
    (net (code "108") (name "unconnected-(D3-C-Pad4)") (class "Default")
      (node (ref "D3") (pin "4") (pinfunction "C_4") (pintype "passive"))
    )
    (net (code "109") (name "unconnected-(D3-CA1-Pad3)") (class "Default")
      (node (ref "D3") (pin "3") (pinfunction "CA1_3") (pintype "passive"))
    )
    (net (code "110") (name "unconnected-(D3-D-Pad2)") (class "Default")
      (node (ref "D3") (pin "2") (pinfunction "D_2") (pintype "passive"))
    )
    (net (code "111") (name "unconnected-(D3-DP-Pad5)") (class "Default")
      (node (ref "D3") (pin "5") (pinfunction "DP_5") (pintype "passive"))
    )
    (net (code "112") (name "unconnected-(D3-E-Pad1)") (class "Default")
      (node (ref "D3") (pin "1") (pinfunction "E_1") (pintype "passive"))
    )
    (net (code "113") (name "unconnected-(D3-F-Pad9)") (class "Default")
      (node (ref "D3") (pin "9") (pinfunction "F_9") (pintype "passive"))
    )
    (net (code "114") (name "unconnected-(D3-G-Pad10)") (class "Default")
      (node (ref "D3") (pin "10") (pinfunction "G_10") (pintype "passive"))
    )
    (net (code "115") (name "unconnected-(D4-A-Pad7)") (class "Default")
      (node (ref "D4") (pin "7") (pinfunction "A_7") (pintype "passive"))
    )
    (net (code "116") (name "unconnected-(D4-B-Pad6)") (class "Default")
      (node (ref "D4") (pin "6") (pinfunction "B_6") (pintype "passive"))
    )
    (net (code "117") (name "unconnected-(D4-C-Pad4)") (class "Default")
      (node (ref "D4") (pin "4") (pinfunction "C_4") (pintype "passive"))
    )
    (net (code "118") (name "unconnected-(D4-CA1-Pad3)") (class "Default")
      (node (ref "D4") (pin "3") (pinfunction "CA1_3") (pintype "passive"))
    )
    (net (code "119") (name "unconnected-(D4-D-Pad2)") (class "Default")
      (node (ref "D4") (pin "2") (pinfunction "D_2") (pintype "passive"))
    )
    (net (code "120") (name "unconnected-(D4-DP-Pad5)") (class "Default")
      (node (ref "D4") (pin "5") (pinfunction "DP_5") (pintype "passive"))
    )
    (net (code "121") (name "unconnected-(D4-E-Pad1)") (class "Default")
      (node (ref "D4") (pin "1") (pinfunction "E_1") (pintype "passive"))
    )
    (net (code "122") (name "unconnected-(D4-F-Pad9)") (class "Default")
      (node (ref "D4") (pin "9") (pinfunction "F_9") (pintype "passive"))
    )
    (net (code "123") (name "unconnected-(D4-G-Pad10)") (class "Default")
      (node (ref "D4") (pin "10") (pinfunction "G_10") (pintype "passive"))
    )
    (net (code "124") (name "unconnected-(D5-A-Pad7)") (class "Default")
      (node (ref "D5") (pin "7") (pinfunction "A_7") (pintype "passive"))
    )
    (net (code "125") (name "unconnected-(D5-B-Pad6)") (class "Default")
      (node (ref "D5") (pin "6") (pinfunction "B_6") (pintype "passive"))
    )
    (net (code "126") (name "unconnected-(D5-C-Pad4)") (class "Default")
      (node (ref "D5") (pin "4") (pinfunction "C_4") (pintype "passive"))
    )
    (net (code "127") (name "unconnected-(D5-CA1-Pad3)") (class "Default")
      (node (ref "D5") (pin "3") (pinfunction "CA1_3") (pintype "passive"))
    )
    (net (code "128") (name "unconnected-(D5-D-Pad2)") (class "Default")
      (node (ref "D5") (pin "2") (pinfunction "D_2") (pintype "passive"))
    )
    (net (code "129") (name "unconnected-(D5-DP-Pad5)") (class "Default")
      (node (ref "D5") (pin "5") (pinfunction "DP_5") (pintype "passive"))
    )
    (net (code "130") (name "unconnected-(D5-E-Pad1)") (class "Default")
      (node (ref "D5") (pin "1") (pinfunction "E_1") (pintype "passive"))
    )
    (net (code "131") (name "unconnected-(D5-F-Pad9)") (class "Default")
      (node (ref "D5") (pin "9") (pinfunction "F_9") (pintype "passive"))
    )
    (net (code "132") (name "unconnected-(D5-G-Pad10)") (class "Default")
      (node (ref "D5") (pin "10") (pinfunction "G_10") (pintype "passive"))
    )
    (net (code "133") (name "unconnected-(D6-A-Pad7)") (class "Default")
      (node (ref "D6") (pin "7") (pinfunction "A_7") (pintype "passive"))
    )
    (net (code "134") (name "unconnected-(D6-B-Pad6)") (class "Default")
      (node (ref "D6") (pin "6") (pinfunction "B_6") (pintype "passive"))
    )
    (net (code "135") (name "unconnected-(D6-C-Pad4)") (class "Default")
      (node (ref "D6") (pin "4") (pinfunction "C_4") (pintype "passive"))
    )
    (net (code "136") (name "unconnected-(D6-CA1-Pad3)") (class "Default")
      (node (ref "D6") (pin "3") (pinfunction "CA1_3") (pintype "passive"))
    )
    (net (code "137") (name "unconnected-(D6-D-Pad2)") (class "Default")
      (node (ref "D6") (pin "2") (pinfunction "D_2") (pintype "passive"))
    )
    (net (code "138") (name "unconnected-(D6-DP-Pad5)") (class "Default")
      (node (ref "D6") (pin "5") (pinfunction "DP_5") (pintype "passive"))
    )
    (net (code "139") (name "unconnected-(D6-E-Pad1)") (class "Default")
      (node (ref "D6") (pin "1") (pinfunction "E_1") (pintype "passive"))
    )
    (net (code "140") (name "unconnected-(D6-F-Pad9)") (class "Default")
      (node (ref "D6") (pin "9") (pinfunction "F_9") (pintype "passive"))
    )
    (net (code "141") (name "unconnected-(D6-G-Pad10)") (class "Default")
      (node (ref "D6") (pin "10") (pinfunction "G_10") (pintype "passive"))
    )
    (net (code "142") (name "unconnected-(D7-A-Pad7)") (class "Default")
      (node (ref "D7") (pin "7") (pinfunction "A_7") (pintype "passive"))
    )
    (net (code "143") (name "unconnected-(D7-B-Pad6)") (class "Default")
      (node (ref "D7") (pin "6") (pinfunction "B_6") (pintype "passive"))
    )
    (net (code "144") (name "unconnected-(D7-C-Pad4)") (class "Default")
      (node (ref "D7") (pin "4") (pinfunction "C_4") (pintype "passive"))
    )
    (net (code "145") (name "unconnected-(D7-CA1-Pad3)") (class "Default")
      (node (ref "D7") (pin "3") (pinfunction "CA1_3") (pintype "passive"))
    )
    (net (code "146") (name "unconnected-(D7-D-Pad2)") (class "Default")
      (node (ref "D7") (pin "2") (pinfunction "D_2") (pintype "passive"))
    )
    (net (code "147") (name "unconnected-(D7-DP-Pad5)") (class "Default")
      (node (ref "D7") (pin "5") (pinfunction "DP_5") (pintype "passive"))
    )
    (net (code "148") (name "unconnected-(D7-E-Pad1)") (class "Default")
      (node (ref "D7") (pin "1") (pinfunction "E_1") (pintype "passive"))
    )
    (net (code "149") (name "unconnected-(D7-F-Pad9)") (class "Default")
      (node (ref "D7") (pin "9") (pinfunction "F_9") (pintype "passive"))
    )
    (net (code "150") (name "unconnected-(D7-G-Pad10)") (class "Default")
      (node (ref "D7") (pin "10") (pinfunction "G_10") (pintype "passive"))
    )
    (net (code "151") (name "unconnected-(D8-A-Pad7)") (class "Default")
      (node (ref "D8") (pin "7") (pinfunction "A_7") (pintype "passive"))
    )
    (net (code "152") (name "unconnected-(D8-B-Pad6)") (class "Default")
      (node (ref "D8") (pin "6") (pinfunction "B_6") (pintype "passive"))
    )
    (net (code "153") (name "unconnected-(D8-C-Pad4)") (class "Default")
      (node (ref "D8") (pin "4") (pinfunction "C_4") (pintype "passive"))
    )
    (net (code "154") (name "unconnected-(D8-CA1-Pad3)") (class "Default")
      (node (ref "D8") (pin "3") (pinfunction "CA1_3") (pintype "passive"))
    )
    (net (code "155") (name "unconnected-(D8-D-Pad2)") (class "Default")
      (node (ref "D8") (pin "2") (pinfunction "D_2") (pintype "passive"))
    )
    (net (code "156") (name "unconnected-(D8-DP-Pad5)") (class "Default")
      (node (ref "D8") (pin "5") (pinfunction "DP_5") (pintype "passive"))
    )
    (net (code "157") (name "unconnected-(D8-E-Pad1)") (class "Default")
      (node (ref "D8") (pin "1") (pinfunction "E_1") (pintype "passive"))
    )
    (net (code "158") (name "unconnected-(D8-F-Pad9)") (class "Default")
      (node (ref "D8") (pin "9") (pinfunction "F_9") (pintype "passive"))
    )
    (net (code "159") (name "unconnected-(D8-G-Pad10)") (class "Default")
      (node (ref "D8") (pin "10") (pinfunction "G_10") (pintype "passive"))
    )
    (net (code "160") (name "unconnected-(D9-A-Pad7)") (class "Default")
      (node (ref "D9") (pin "7") (pinfunction "A_7") (pintype "passive"))
    )
    (net (code "161") (name "unconnected-(D9-B-Pad6)") (class "Default")
      (node (ref "D9") (pin "6") (pinfunction "B_6") (pintype "passive"))
    )
    (net (code "162") (name "unconnected-(D9-C-Pad4)") (class "Default")
      (node (ref "D9") (pin "4") (pinfunction "C_4") (pintype "passive"))
    )
    (net (code "163") (name "unconnected-(D9-CA1-Pad3)") (class "Default")
      (node (ref "D9") (pin "3") (pinfunction "CA1_3") (pintype "passive"))
    )
    (net (code "164") (name "unconnected-(D9-D-Pad2)") (class "Default")
      (node (ref "D9") (pin "2") (pinfunction "D_2") (pintype "passive"))
    )
    (net (code "165") (name "unconnected-(D9-DP-Pad5)") (class "Default")
      (node (ref "D9") (pin "5") (pinfunction "DP_5") (pintype "passive"))
    )
    (net (code "166") (name "unconnected-(D9-E-Pad1)") (class "Default")
      (node (ref "D9") (pin "1") (pinfunction "E_1") (pintype "passive"))
    )
    (net (code "167") (name "unconnected-(D9-F-Pad9)") (class "Default")
      (node (ref "D9") (pin "9") (pinfunction "F_9") (pintype "passive"))
    )
    (net (code "168") (name "unconnected-(D9-G-Pad10)") (class "Default")
      (node (ref "D9") (pin "10") (pinfunction "G_10") (pintype "passive"))
    )
    (net (code "169") (name "unconnected-(D10-A-Pad7)") (class "Default")
      (node (ref "D10") (pin "7") (pinfunction "A_7") (pintype "passive"))
    )
    (net (code "170") (name "unconnected-(D10-B-Pad6)") (class "Default")
      (node (ref "D10") (pin "6") (pinfunction "B_6") (pintype "passive"))
    )
    (net (code "171") (name "unconnected-(D10-C-Pad4)") (class "Default")
      (node (ref "D10") (pin "4") (pinfunction "C_4") (pintype "passive"))
    )
    (net (code "172") (name "unconnected-(D10-CA1-Pad3)") (class "Default")
      (node (ref "D10") (pin "3") (pinfunction "CA1_3") (pintype "passive"))
    )
    (net (code "173") (name "unconnected-(D10-D-Pad2)") (class "Default")
      (node (ref "D10") (pin "2") (pinfunction "D_2") (pintype "passive"))
    )
    (net (code "174") (name "unconnected-(D10-DP-Pad5)") (class "Default")
      (node (ref "D10") (pin "5") (pinfunction "DP_5") (pintype "passive"))
    )
    (net (code "175") (name "unconnected-(D10-E-Pad1)") (class "Default")
      (node (ref "D10") (pin "1") (pinfunction "E_1") (pintype "passive"))
    )
    (net (code "176") (name "unconnected-(D10-F-Pad9)") (class "Default")
      (node (ref "D10") (pin "9") (pinfunction "F_9") (pintype "passive"))
    )
    (net (code "177") (name "unconnected-(D10-G-Pad10)") (class "Default")
      (node (ref "D10") (pin "10") (pinfunction "G_10") (pintype "passive"))
    )
    (net (code "178") (name "unconnected-(D11-A-Pad7)") (class "Default")
      (node (ref "D11") (pin "7") (pinfunction "A_7") (pintype "passive"))
    )
    (net (code "179") (name "unconnected-(D11-B-Pad6)") (class "Default")
      (node (ref "D11") (pin "6") (pinfunction "B_6") (pintype "passive"))
    )
    (net (code "180") (name "unconnected-(D11-C-Pad4)") (class "Default")
      (node (ref "D11") (pin "4") (pinfunction "C_4") (pintype "passive"))
    )
    (net (code "181") (name "unconnected-(D11-CA1-Pad3)") (class "Default")
      (node (ref "D11") (pin "3") (pinfunction "CA1_3") (pintype "passive"))
    )
    (net (code "182") (name "unconnected-(D11-D-Pad2)") (class "Default")
      (node (ref "D11") (pin "2") (pinfunction "D_2") (pintype "passive"))
    )
    (net (code "183") (name "unconnected-(D11-DP-Pad5)") (class "Default")
      (node (ref "D11") (pin "5") (pinfunction "DP_5") (pintype "passive"))
    )
    (net (code "184") (name "unconnected-(D11-E-Pad1)") (class "Default")
      (node (ref "D11") (pin "1") (pinfunction "E_1") (pintype "passive"))
    )
    (net (code "185") (name "unconnected-(D11-F-Pad9)") (class "Default")
      (node (ref "D11") (pin "9") (pinfunction "F_9") (pintype "passive"))
    )
    (net (code "186") (name "unconnected-(D11-G-Pad10)") (class "Default")
      (node (ref "D11") (pin "10") (pinfunction "G_10") (pintype "passive"))
    )
    (net (code "187") (name "unconnected-(D12-A-Pad7)") (class "Default")
      (node (ref "D12") (pin "7") (pinfunction "A_7") (pintype "passive"))
    )
    (net (code "188") (name "unconnected-(D12-B-Pad6)") (class "Default")
      (node (ref "D12") (pin "6") (pinfunction "B_6") (pintype "passive"))
    )
    (net (code "189") (name "unconnected-(D12-C-Pad4)") (class "Default")
      (node (ref "D12") (pin "4") (pinfunction "C_4") (pintype "passive"))
    )
    (net (code "190") (name "unconnected-(D12-CA1-Pad3)") (class "Default")
      (node (ref "D12") (pin "3") (pinfunction "CA1_3") (pintype "passive"))
    )
    (net (code "191") (name "unconnected-(D12-D-Pad2)") (class "Default")
      (node (ref "D12") (pin "2") (pinfunction "D_2") (pintype "passive"))
    )
    (net (code "192") (name "unconnected-(D12-DP-Pad5)") (class "Default")
      (node (ref "D12") (pin "5") (pinfunction "DP_5") (pintype "passive"))
    )
    (net (code "193") (name "unconnected-(D12-E-Pad1)") (class "Default")
      (node (ref "D12") (pin "1") (pinfunction "E_1") (pintype "passive"))
    )
    (net (code "194") (name "unconnected-(D12-F-Pad9)") (class "Default")
      (node (ref "D12") (pin "9") (pinfunction "F_9") (pintype "passive"))
    )
    (net (code "195") (name "unconnected-(D12-G-Pad10)") (class "Default")
      (node (ref "D12") (pin "10") (pinfunction "G_10") (pintype "passive"))
    )
    (net (code "196") (name "unconnected-(D13-PadA)") (class "Default")
      (node (ref "D13") (pin "A") (pinfunction "A_A") (pintype "passive"))
    )
    (net (code "197") (name "unconnected-(D13-PadC)") (class "Default")
      (node (ref "D13") (pin "C") (pinfunction "C_C") (pintype "passive"))
    )
    (net (code "198") (name "unconnected-(G1-+-Pad+@1)") (class "Default")
      (node (ref "G1") (pin "+@1") (pinfunction "+_+@1") (pintype "passive"))
    )
    (net (code "199") (name "unconnected-(IC2A-QE-Pad4)") (class "Default")
      (node (ref "IC2") (pin "4") (pinfunction "QE_4") (pintype "tri_state"))
    )
    (net (code "200") (name "unconnected-(IC2A-QF-Pad5)") (class "Default")
      (node (ref "IC2") (pin "5") (pinfunction "QF_5") (pintype "tri_state"))
    )
    (net (code "201") (name "unconnected-(IC2A-QG-Pad6)") (class "Default")
      (node (ref "IC2") (pin "6") (pinfunction "QG_6") (pintype "tri_state"))
    )
    (net (code "202") (name "unconnected-(IC2A-QH*-Pad9)") (class "Default")
      (node (ref "IC2") (pin "9") (pinfunction "QH*_9") (pintype "tri_state"))
    )
    (net (code "203") (name "unconnected-(IC2A-QH-Pad7)") (class "Default")
      (node (ref "IC2") (pin "7") (pinfunction "QH_7") (pintype "tri_state"))
    )
    (net (code "204") (name "unconnected-(JP1-Pad2)") (class "Default")
      (node (ref "JP1") (pin "2") (pinfunction "2_2") (pintype "passive"))
    )
    (net (code "205") (name "unconnected-(RTC1-32KHZ-Pad1)") (class "Default")
      (node (ref "RTC1") (pin "1") (pinfunction "32KHZ_1") (pintype "output"))
    )
    (net (code "206") (name "unconnected-(RTC1-RST-Pad4)") (class "Default")
      (node (ref "RTC1") (pin "4") (pinfunction "RST_4") (pintype "bidirectional"))
    )
    (net (code "207") (name "unconnected-(RTC1-SQW-Pad3)") (class "Default")
      (node (ref "RTC1") (pin "3") (pinfunction "SQW_3") (pintype "output"))
    )
    (net (code "208") (name "unconnected-(S6-O-Pad1)") (class "Default")
      (node (ref "S6") (pin "1") (pinfunction "O_1") (pintype "passive"))
    )
    (net (code "209") (name "unconnected-(U1-PB6(XTAL1{slash}TOSC1)-Pad9)") (class "Default")
      (node (ref "U1") (pin "9") (pinfunction "PB6(XTAL1/TOSC1)_9") (pintype "bidirectional"))
    )
    (net (code "210") (name "unconnected-(U1-PB7(XTAL2{slash}TOSC2)-Pad10)") (class "Default")
      (node (ref "U1") (pin "10") (pinfunction "PB7(XTAL2/TOSC2)_10") (pintype "bidirectional"))
    )
    (net (code "211") (name "unconnected-(U1-PD6(AIN0)-Pad12)") (class "Default")
      (node (ref "U1") (pin "12") (pinfunction "PD6(AIN0)_12") (pintype "bidirectional"))
    )
  )
)
